# amelia_A_v1.net
KiCad netlist of a schematic drawn in EAGLE
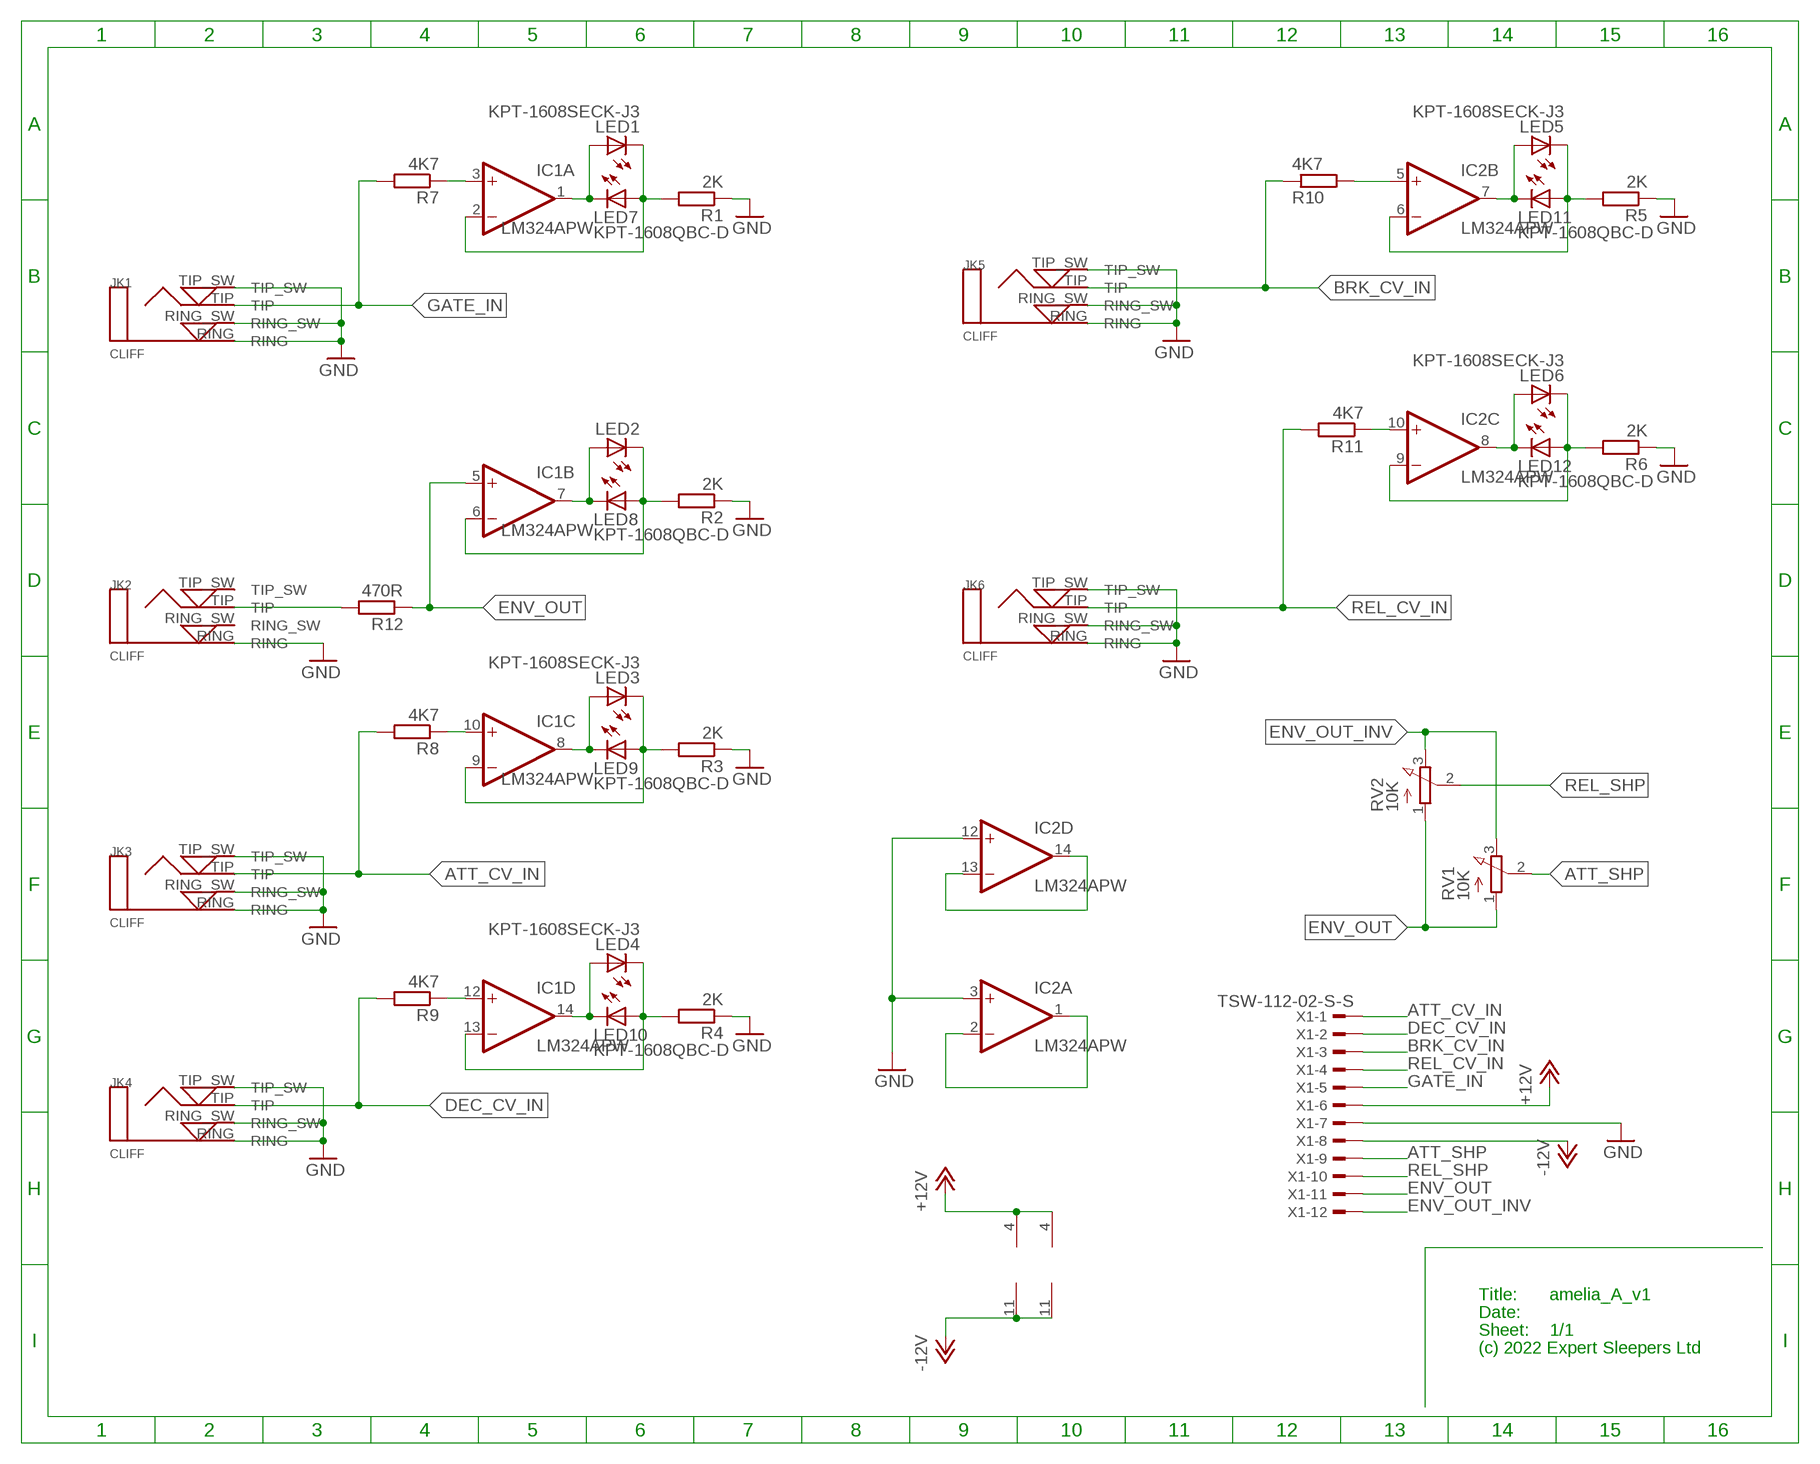
[diagram p0: schematic, sheet 1]

(export (version "E")
  (design (tool "Eeschema 10.0.6"))
  (components
    (comp (ref "IC1")
      (value "LM324APW")
      (footprint "eagle-import:PW_R-PDSO-G14")
      (libsource (lib "eagle-import") (part "TL074PW"))
    )
    (comp (ref "IC2")
      (value "LM324APW")
      (footprint "eagle-import:PW_R-PDSO-G14")
      (libsource (lib "eagle-import") (part "TL074PW"))
    )
    (comp (ref "JK1")
      (value "CLIFF")
      (footprint "eagle-import:CLIFF3.5MMPCB")
      (libsource (lib "eagle-import") (part "CLIFF3.5MM_PCB_SW_JK"))
    )
    (comp (ref "JK2")
      (value "CLIFF")
      (footprint "eagle-import:CLIFF3.5MMPCB")
      (libsource (lib "eagle-import") (part "CLIFF3.5MM_PCB_SW_JK"))
    )
    (comp (ref "JK3")
      (value "CLIFF")
      (footprint "eagle-import:CLIFF3.5MMPCB")
      (libsource (lib "eagle-import") (part "CLIFF3.5MM_PCB_SW_JK"))
    )
    (comp (ref "JK4")
      (value "CLIFF")
      (footprint "eagle-import:CLIFF3.5MMPCB")
      (libsource (lib "eagle-import") (part "CLIFF3.5MM_PCB_SW_JK"))
    )
    (comp (ref "JK5")
      (value "CLIFF")
      (footprint "eagle-import:CLIFF3.5MMPCB")
      (libsource (lib "eagle-import") (part "CLIFF3.5MM_PCB_SW_JK"))
    )
    (comp (ref "JK6")
      (value "CLIFF")
      (footprint "eagle-import:CLIFF3.5MMPCB")
      (libsource (lib "eagle-import") (part "CLIFF3.5MM_PCB_SW_JK"))
    )
    (comp (ref "LED1")
      (value "KPT-1608SECK-J3")
      (footprint "eagle-import:CHIPLED_0603_LEFT")
      (libsource (lib "eagle-import") (part "KPT-1608SECK-J3"))
    )
    (comp (ref "LED2")
      (value "KPT-1608SECK-J3")
      (footprint "eagle-import:CHIPLED_0603_LEFT")
      (libsource (lib "eagle-import") (part "KPT-1608SECK-J3"))
    )
    (comp (ref "LED3")
      (value "KPT-1608SECK-J3")
      (footprint "eagle-import:CHIPLED_0603_LEFT")
      (libsource (lib "eagle-import") (part "KPT-1608SECK-J3"))
    )
    (comp (ref "LED4")
      (value "KPT-1608SECK-J3")
      (footprint "eagle-import:CHIPLED_0603_LEFT")
      (libsource (lib "eagle-import") (part "KPT-1608SECK-J3"))
    )
    (comp (ref "LED5")
      (value "KPT-1608SECK-J3")
      (footprint "eagle-import:CHIPLED_0603_LEFT")
      (libsource (lib "eagle-import") (part "KPT-1608SECK-J3"))
    )
    (comp (ref "LED6")
      (value "KPT-1608SECK-J3")
      (footprint "eagle-import:CHIPLED_0603_LEFT")
      (libsource (lib "eagle-import") (part "KPT-1608SECK-J3"))
    )
    (comp (ref "LED7")
      (value "KPT-1608QBC-D")
      (footprint "eagle-import:CHIPLED_0603_RIGHT")
      (libsource (lib "eagle-import") (part "KPT-1608QBC-D"))
    )
    (comp (ref "LED8")
      (value "KPT-1608QBC-D")
      (footprint "eagle-import:CHIPLED_0603_RIGHT")
      (libsource (lib "eagle-import") (part "KPT-1608QBC-D"))
    )
    (comp (ref "LED9")
      (value "KPT-1608QBC-D")
      (footprint "eagle-import:CHIPLED_0603_RIGHT")
      (libsource (lib "eagle-import") (part "KPT-1608QBC-D"))
    )
    (comp (ref "LED10")
      (value "KPT-1608QBC-D")
      (footprint "eagle-import:CHIPLED_0603_RIGHT")
      (libsource (lib "eagle-import") (part "KPT-1608QBC-D"))
    )
    (comp (ref "LED11")
      (value "KPT-1608QBC-D")
      (footprint "eagle-import:CHIPLED_0603_RIGHT")
      (libsource (lib "eagle-import") (part "KPT-1608QBC-D"))
    )
    (comp (ref "LED12")
      (value "KPT-1608QBC-D")
      (footprint "eagle-import:CHIPLED_0603_RIGHT")
      (libsource (lib "eagle-import") (part "KPT-1608QBC-D"))
    )
    (comp (ref "R1")
      (value "2K")
      (footprint "eagle-import:R1206")
      (libsource (lib "eagle-import") (part "R-EU_R1206"))
    )
    (comp (ref "R2")
      (value "2K")
      (footprint "eagle-import:R1206")
      (libsource (lib "eagle-import") (part "R-EU_R1206"))
    )
    (comp (ref "R3")
      (value "2K")
      (footprint "eagle-import:R1206")
      (libsource (lib "eagle-import") (part "R-EU_R1206"))
    )
    (comp (ref "R4")
      (value "2K")
      (footprint "eagle-import:R1206")
      (libsource (lib "eagle-import") (part "R-EU_R1206"))
    )
    (comp (ref "R5")
      (value "2K")
      (footprint "eagle-import:R1206")
      (libsource (lib "eagle-import") (part "R-EU_R1206"))
    )
    (comp (ref "R6")
      (value "2K")
      (footprint "eagle-import:R1206")
      (libsource (lib "eagle-import") (part "R-EU_R1206"))
    )
    (comp (ref "R7")
      (value "4K7")
      (footprint "eagle-import:R1206")
      (libsource (lib "eagle-import") (part "R-EU_R1206"))
    )
    (comp (ref "R8")
      (value "4K7")
      (footprint "eagle-import:R1206")
      (libsource (lib "eagle-import") (part "R-EU_R1206"))
    )
    (comp (ref "R9")
      (value "4K7")
      (footprint "eagle-import:R1206")
      (libsource (lib "eagle-import") (part "R-EU_R1206"))
    )
    (comp (ref "R10")
      (value "4K7")
      (footprint "eagle-import:R1206")
      (libsource (lib "eagle-import") (part "R-EU_R1206"))
    )
    (comp (ref "R11")
      (value "4K7")
      (footprint "eagle-import:R1206")
      (libsource (lib "eagle-import") (part "R-EU_R1206"))
    )
    (comp (ref "R12")
      (value "470R")
      (footprint "eagle-import:R1206")
      (libsource (lib "eagle-import") (part "R-EU_R1206"))
    )
    (comp (ref "RV1")
      (value "10K")
      (footprint "eagle-import:RA0901NOX0A-VA1-131")
      (libsource (lib "eagle-import") (part "RA0901NOX0A-VA1-131"))
    )
    (comp (ref "RV2")
      (value "10K")
      (footprint "eagle-import:RA0901NOX0A-VA1-131")
      (libsource (lib "eagle-import") (part "RA0901NOX0A-VA1-131"))
    )
    (comp (ref "X1")
      (value "TSW-112-02-S-S")
      (footprint "eagle-import:TSW-112-02-S-S")
      (libsource (lib "eagle-import") (part "TSW-112-02-S-S"))
    )
  )
  (nets
    (net (code "1") (name "+12V") (class "Default")
      (node (ref "IC1") (pin "4") (pinfunction "V+_4") (pintype "power_in"))
      (node (ref "IC2") (pin "4") (pinfunction "V+_4") (pintype "power_in"))
      (node (ref "X1") (pin "6") (pinfunction "1_6") (pintype "passive"))
    )
    (net (code "2") (name "-12V") (class "Default")
      (node (ref "IC1") (pin "11") (pinfunction "V-_11") (pintype "power_in"))
      (node (ref "IC2") (pin "11") (pinfunction "V-_11") (pintype "power_in"))
      (node (ref "X1") (pin "8") (pinfunction "1_8") (pintype "passive"))
    )
    (net (code "3") (name "ATT_CV_IN") (class "Default")
      (node (ref "JK3") (pin "TIP") (pinfunction "TIP_TIP") (pintype "bidirectional"))
      (node (ref "R8") (pin "2") (pinfunction "2_2") (pintype "passive"))
      (node (ref "X1") (pin "1") (pinfunction "1_1") (pintype "passive"))
    )
    (net (code "4") (name "ATT_SHP") (class "Default")
      (node (ref "RV1") (pin "2") (pinfunction "S_2") (pintype "passive"))
      (node (ref "X1") (pin "9") (pinfunction "1_9") (pintype "passive"))
    )
    (net (code "5") (name "BRK_CV_IN") (class "Default")
      (node (ref "JK5") (pin "TIP") (pinfunction "TIP_TIP") (pintype "bidirectional"))
      (node (ref "R10") (pin "1") (pinfunction "1_1") (pintype "passive"))
      (node (ref "X1") (pin "3") (pinfunction "1_3") (pintype "passive"))
    )
    (net (code "6") (name "DEC_CV_IN") (class "Default")
      (node (ref "JK4") (pin "TIP") (pinfunction "TIP_TIP") (pintype "bidirectional"))
      (node (ref "R9") (pin "2") (pinfunction "2_2") (pintype "passive"))
      (node (ref "X1") (pin "2") (pinfunction "1_2") (pintype "passive"))
    )
    (net (code "7") (name "ENV_OUT") (class "Default")
      (node (ref "IC1") (pin "5") (pinfunction "+IN_5") (pintype "input"))
      (node (ref "R12") (pin "1") (pinfunction "1_1") (pintype "passive"))
      (node (ref "RV1") (pin "1") (pinfunction "A_1") (pintype "passive"))
      (node (ref "RV2") (pin "1") (pinfunction "A_1") (pintype "passive"))
      (node (ref "X1") (pin "11") (pinfunction "1_11") (pintype "passive"))
    )
    (net (code "8") (name "ENV_OUT_INV") (class "Default")
      (node (ref "RV1") (pin "3") (pinfunction "E_3") (pintype "passive"))
      (node (ref "RV2") (pin "3") (pinfunction "E_3") (pintype "passive"))
      (node (ref "X1") (pin "12") (pinfunction "1_12") (pintype "passive"))
    )
    (net (code "9") (name "GATE_IN") (class "Default")
      (node (ref "JK1") (pin "TIP") (pinfunction "TIP_TIP") (pintype "bidirectional"))
      (node (ref "R7") (pin "2") (pinfunction "2_2") (pintype "passive"))
      (node (ref "X1") (pin "5") (pinfunction "1_5") (pintype "passive"))
    )
    (net (code "10") (name "GND") (class "Default")
      (node (ref "IC2") (pin "12") (pinfunction "+IN_12") (pintype "input"))
      (node (ref "IC2") (pin "3") (pinfunction "+IN_3") (pintype "input"))
      (node (ref "JK1") (pin "RING") (pinfunction "RING_RING") (pintype "bidirectional"))
      (node (ref "JK1") (pin "RING_SW") (pinfunction "RING_SW_RING_SW") (pintype "bidirectional"))
      (node (ref "JK1") (pin "TIP_SW") (pinfunction "TIP_SW_TIP_SW") (pintype "bidirectional"))
      (node (ref "JK2") (pin "RING") (pinfunction "RING_RING") (pintype "bidirectional"))
      (node (ref "JK3") (pin "RING") (pinfunction "RING_RING") (pintype "bidirectional"))
      (node (ref "JK3") (pin "RING_SW") (pinfunction "RING_SW_RING_SW") (pintype "bidirectional"))
      (node (ref "JK3") (pin "TIP_SW") (pinfunction "TIP_SW_TIP_SW") (pintype "bidirectional"))
      (node (ref "JK4") (pin "RING") (pinfunction "RING_RING") (pintype "bidirectional"))
      (node (ref "JK4") (pin "RING_SW") (pinfunction "RING_SW_RING_SW") (pintype "bidirectional"))
      (node (ref "JK4") (pin "TIP_SW") (pinfunction "TIP_SW_TIP_SW") (pintype "bidirectional"))
      (node (ref "JK5") (pin "RING") (pinfunction "RING_RING") (pintype "bidirectional"))
      (node (ref "JK5") (pin "RING_SW") (pinfunction "RING_SW_RING_SW") (pintype "bidirectional"))
      (node (ref "JK5") (pin "TIP_SW") (pinfunction "TIP_SW_TIP_SW") (pintype "bidirectional"))
      (node (ref "JK6") (pin "RING") (pinfunction "RING_RING") (pintype "bidirectional"))
      (node (ref "JK6") (pin "RING_SW") (pinfunction "RING_SW_RING_SW") (pintype "bidirectional"))
      (node (ref "JK6") (pin "TIP_SW") (pinfunction "TIP_SW_TIP_SW") (pintype "bidirectional"))
      (node (ref "R1") (pin "1") (pinfunction "1_1") (pintype "passive"))
      (node (ref "R2") (pin "1") (pinfunction "1_1") (pintype "passive"))
      (node (ref "R3") (pin "1") (pinfunction "1_1") (pintype "passive"))
      (node (ref "R4") (pin "1") (pinfunction "1_1") (pintype "passive"))
      (node (ref "R5") (pin "1") (pinfunction "1_1") (pintype "passive"))
      (node (ref "R6") (pin "1") (pinfunction "1_1") (pintype "passive"))
      (node (ref "X1") (pin "7") (pinfunction "1_7") (pintype "passive"))
    )
    (net (code "11") (name "Net-(IC1A-+IN)") (class "Default")
      (node (ref "IC1") (pin "3") (pinfunction "+IN_3") (pintype "input"))
      (node (ref "R7") (pin "1") (pinfunction "1_1") (pintype "passive"))
    )
    (net (code "12") (name "Net-(IC1A--IN)") (class "Default")
      (node (ref "IC1") (pin "2") (pinfunction "-IN_2") (pintype "input"))
      (node (ref "LED1") (pin "1") (pinfunction "C_1") (pintype "passive"))
      (node (ref "LED7") (pin "1") (pinfunction "A_1") (pintype "passive"))
      (node (ref "R1") (pin "2") (pinfunction "2_2") (pintype "passive"))
    )
    (net (code "13") (name "Net-(IC1A-OUT)") (class "Default")
      (node (ref "IC1") (pin "1") (pinfunction "OUT_1") (pintype "output"))
      (node (ref "LED1") (pin "2") (pinfunction "A_2") (pintype "passive"))
      (node (ref "LED7") (pin "2") (pinfunction "C_2") (pintype "passive"))
    )
    (net (code "14") (name "Net-(IC1B--IN)") (class "Default")
      (node (ref "IC1") (pin "6") (pinfunction "-IN_6") (pintype "input"))
      (node (ref "LED2") (pin "1") (pinfunction "C_1") (pintype "passive"))
      (node (ref "LED8") (pin "1") (pinfunction "A_1") (pintype "passive"))
      (node (ref "R2") (pin "2") (pinfunction "2_2") (pintype "passive"))
    )
    (net (code "15") (name "Net-(IC1B-OUT)") (class "Default")
      (node (ref "IC1") (pin "7") (pinfunction "OUT_7") (pintype "output"))
      (node (ref "LED2") (pin "2") (pinfunction "A_2") (pintype "passive"))
      (node (ref "LED8") (pin "2") (pinfunction "C_2") (pintype "passive"))
    )
    (net (code "16") (name "Net-(IC1C-+IN)") (class "Default")
      (node (ref "IC1") (pin "10") (pinfunction "+IN_10") (pintype "input"))
      (node (ref "R8") (pin "1") (pinfunction "1_1") (pintype "passive"))
    )
    (net (code "17") (name "Net-(IC1C--IN)") (class "Default")
      (node (ref "IC1") (pin "9") (pinfunction "-IN_9") (pintype "input"))
      (node (ref "LED3") (pin "1") (pinfunction "C_1") (pintype "passive"))
      (node (ref "LED9") (pin "1") (pinfunction "A_1") (pintype "passive"))
      (node (ref "R3") (pin "2") (pinfunction "2_2") (pintype "passive"))
    )
    (net (code "18") (name "Net-(IC1C-OUT)") (class "Default")
      (node (ref "IC1") (pin "8") (pinfunction "OUT_8") (pintype "output"))
      (node (ref "LED3") (pin "2") (pinfunction "A_2") (pintype "passive"))
      (node (ref "LED9") (pin "2") (pinfunction "C_2") (pintype "passive"))
    )
    (net (code "19") (name "Net-(IC1D-+IN)") (class "Default")
      (node (ref "IC1") (pin "12") (pinfunction "+IN_12") (pintype "input"))
      (node (ref "R9") (pin "1") (pinfunction "1_1") (pintype "passive"))
    )
    (net (code "20") (name "Net-(IC1D--IN)") (class "Default")
      (node (ref "IC1") (pin "13") (pinfunction "-IN_13") (pintype "input"))
      (node (ref "LED10") (pin "1") (pinfunction "A_1") (pintype "passive"))
      (node (ref "LED4") (pin "1") (pinfunction "C_1") (pintype "passive"))
      (node (ref "R4") (pin "2") (pinfunction "2_2") (pintype "passive"))
    )
    (net (code "21") (name "Net-(IC1D-OUT)") (class "Default")
      (node (ref "IC1") (pin "14") (pinfunction "OUT_14") (pintype "output"))
      (node (ref "LED10") (pin "2") (pinfunction "C_2") (pintype "passive"))
      (node (ref "LED4") (pin "2") (pinfunction "A_2") (pintype "passive"))
    )
    (net (code "22") (name "Net-(IC2A--IN)") (class "Default")
      (node (ref "IC2") (pin "1") (pinfunction "OUT_1") (pintype "output"))
      (node (ref "IC2") (pin "2") (pinfunction "-IN_2") (pintype "input"))
    )
    (net (code "23") (name "Net-(IC2B-+IN)") (class "Default")
      (node (ref "IC2") (pin "5") (pinfunction "+IN_5") (pintype "input"))
      (node (ref "R10") (pin "2") (pinfunction "2_2") (pintype "passive"))
    )
    (net (code "24") (name "Net-(IC2B--IN)") (class "Default")
      (node (ref "IC2") (pin "6") (pinfunction "-IN_6") (pintype "input"))
      (node (ref "LED11") (pin "1") (pinfunction "A_1") (pintype "passive"))
      (node (ref "LED5") (pin "1") (pinfunction "C_1") (pintype "passive"))
      (node (ref "R5") (pin "2") (pinfunction "2_2") (pintype "passive"))
    )
    (net (code "25") (name "Net-(IC2B-OUT)") (class "Default")
      (node (ref "IC2") (pin "7") (pinfunction "OUT_7") (pintype "output"))
      (node (ref "LED11") (pin "2") (pinfunction "C_2") (pintype "passive"))
      (node (ref "LED5") (pin "2") (pinfunction "A_2") (pintype "passive"))
    )
    (net (code "26") (name "Net-(IC2C-+IN)") (class "Default")
      (node (ref "IC2") (pin "10") (pinfunction "+IN_10") (pintype "input"))
      (node (ref "R11") (pin "1") (pinfunction "1_1") (pintype "passive"))
    )
    (net (code "27") (name "Net-(IC2C--IN)") (class "Default")
      (node (ref "IC2") (pin "9") (pinfunction "-IN_9") (pintype "input"))
      (node (ref "LED12") (pin "1") (pinfunction "A_1") (pintype "passive"))
      (node (ref "LED6") (pin "1") (pinfunction "C_1") (pintype "passive"))
      (node (ref "R6") (pin "2") (pinfunction "2_2") (pintype "passive"))
    )
    (net (code "28") (name "Net-(IC2C-OUT)") (class "Default")
      (node (ref "IC2") (pin "8") (pinfunction "OUT_8") (pintype "output"))
      (node (ref "LED12") (pin "2") (pinfunction "C_2") (pintype "passive"))
      (node (ref "LED6") (pin "2") (pinfunction "A_2") (pintype "passive"))
    )
    (net (code "29") (name "Net-(IC2D--IN)") (class "Default")
      (node (ref "IC2") (pin "13") (pinfunction "-IN_13") (pintype "input"))
      (node (ref "IC2") (pin "14") (pinfunction "OUT_14") (pintype "output"))
    )
    (net (code "30") (name "Net-(JK2-PadTIP)") (class "Default")
      (node (ref "JK2") (pin "TIP") (pinfunction "TIP_TIP") (pintype "bidirectional"))
      (node (ref "R12") (pin "2") (pinfunction "2_2") (pintype "passive"))
    )
    (net (code "31") (name "REL_CV_IN") (class "Default")
      (node (ref "JK6") (pin "TIP") (pinfunction "TIP_TIP") (pintype "bidirectional"))
      (node (ref "R11") (pin "2") (pinfunction "2_2") (pintype "passive"))
      (node (ref "X1") (pin "4") (pinfunction "1_4") (pintype "passive"))
    )
    (net (code "32") (name "REL_SHP") (class "Default")
      (node (ref "RV2") (pin "2") (pinfunction "S_2") (pintype "passive"))
      (node (ref "X1") (pin "10") (pinfunction "1_10") (pintype "passive"))
    )
    (net (code "33") (name "unconnected-(JK2-PadRING_SW)") (class "Default")
      (node (ref "JK2") (pin "RING_SW") (pinfunction "RING_SW_RING_SW") (pintype "bidirectional"))
    )
    (net (code "34") (name "unconnected-(JK2-PadTIP_SW)") (class "Default")
      (node (ref "JK2") (pin "TIP_SW") (pinfunction "TIP_SW_TIP_SW") (pintype "bidirectional"))
    )
  )
)
